# design.net
KiCad netlist of a schematic drawn in Altium Designer
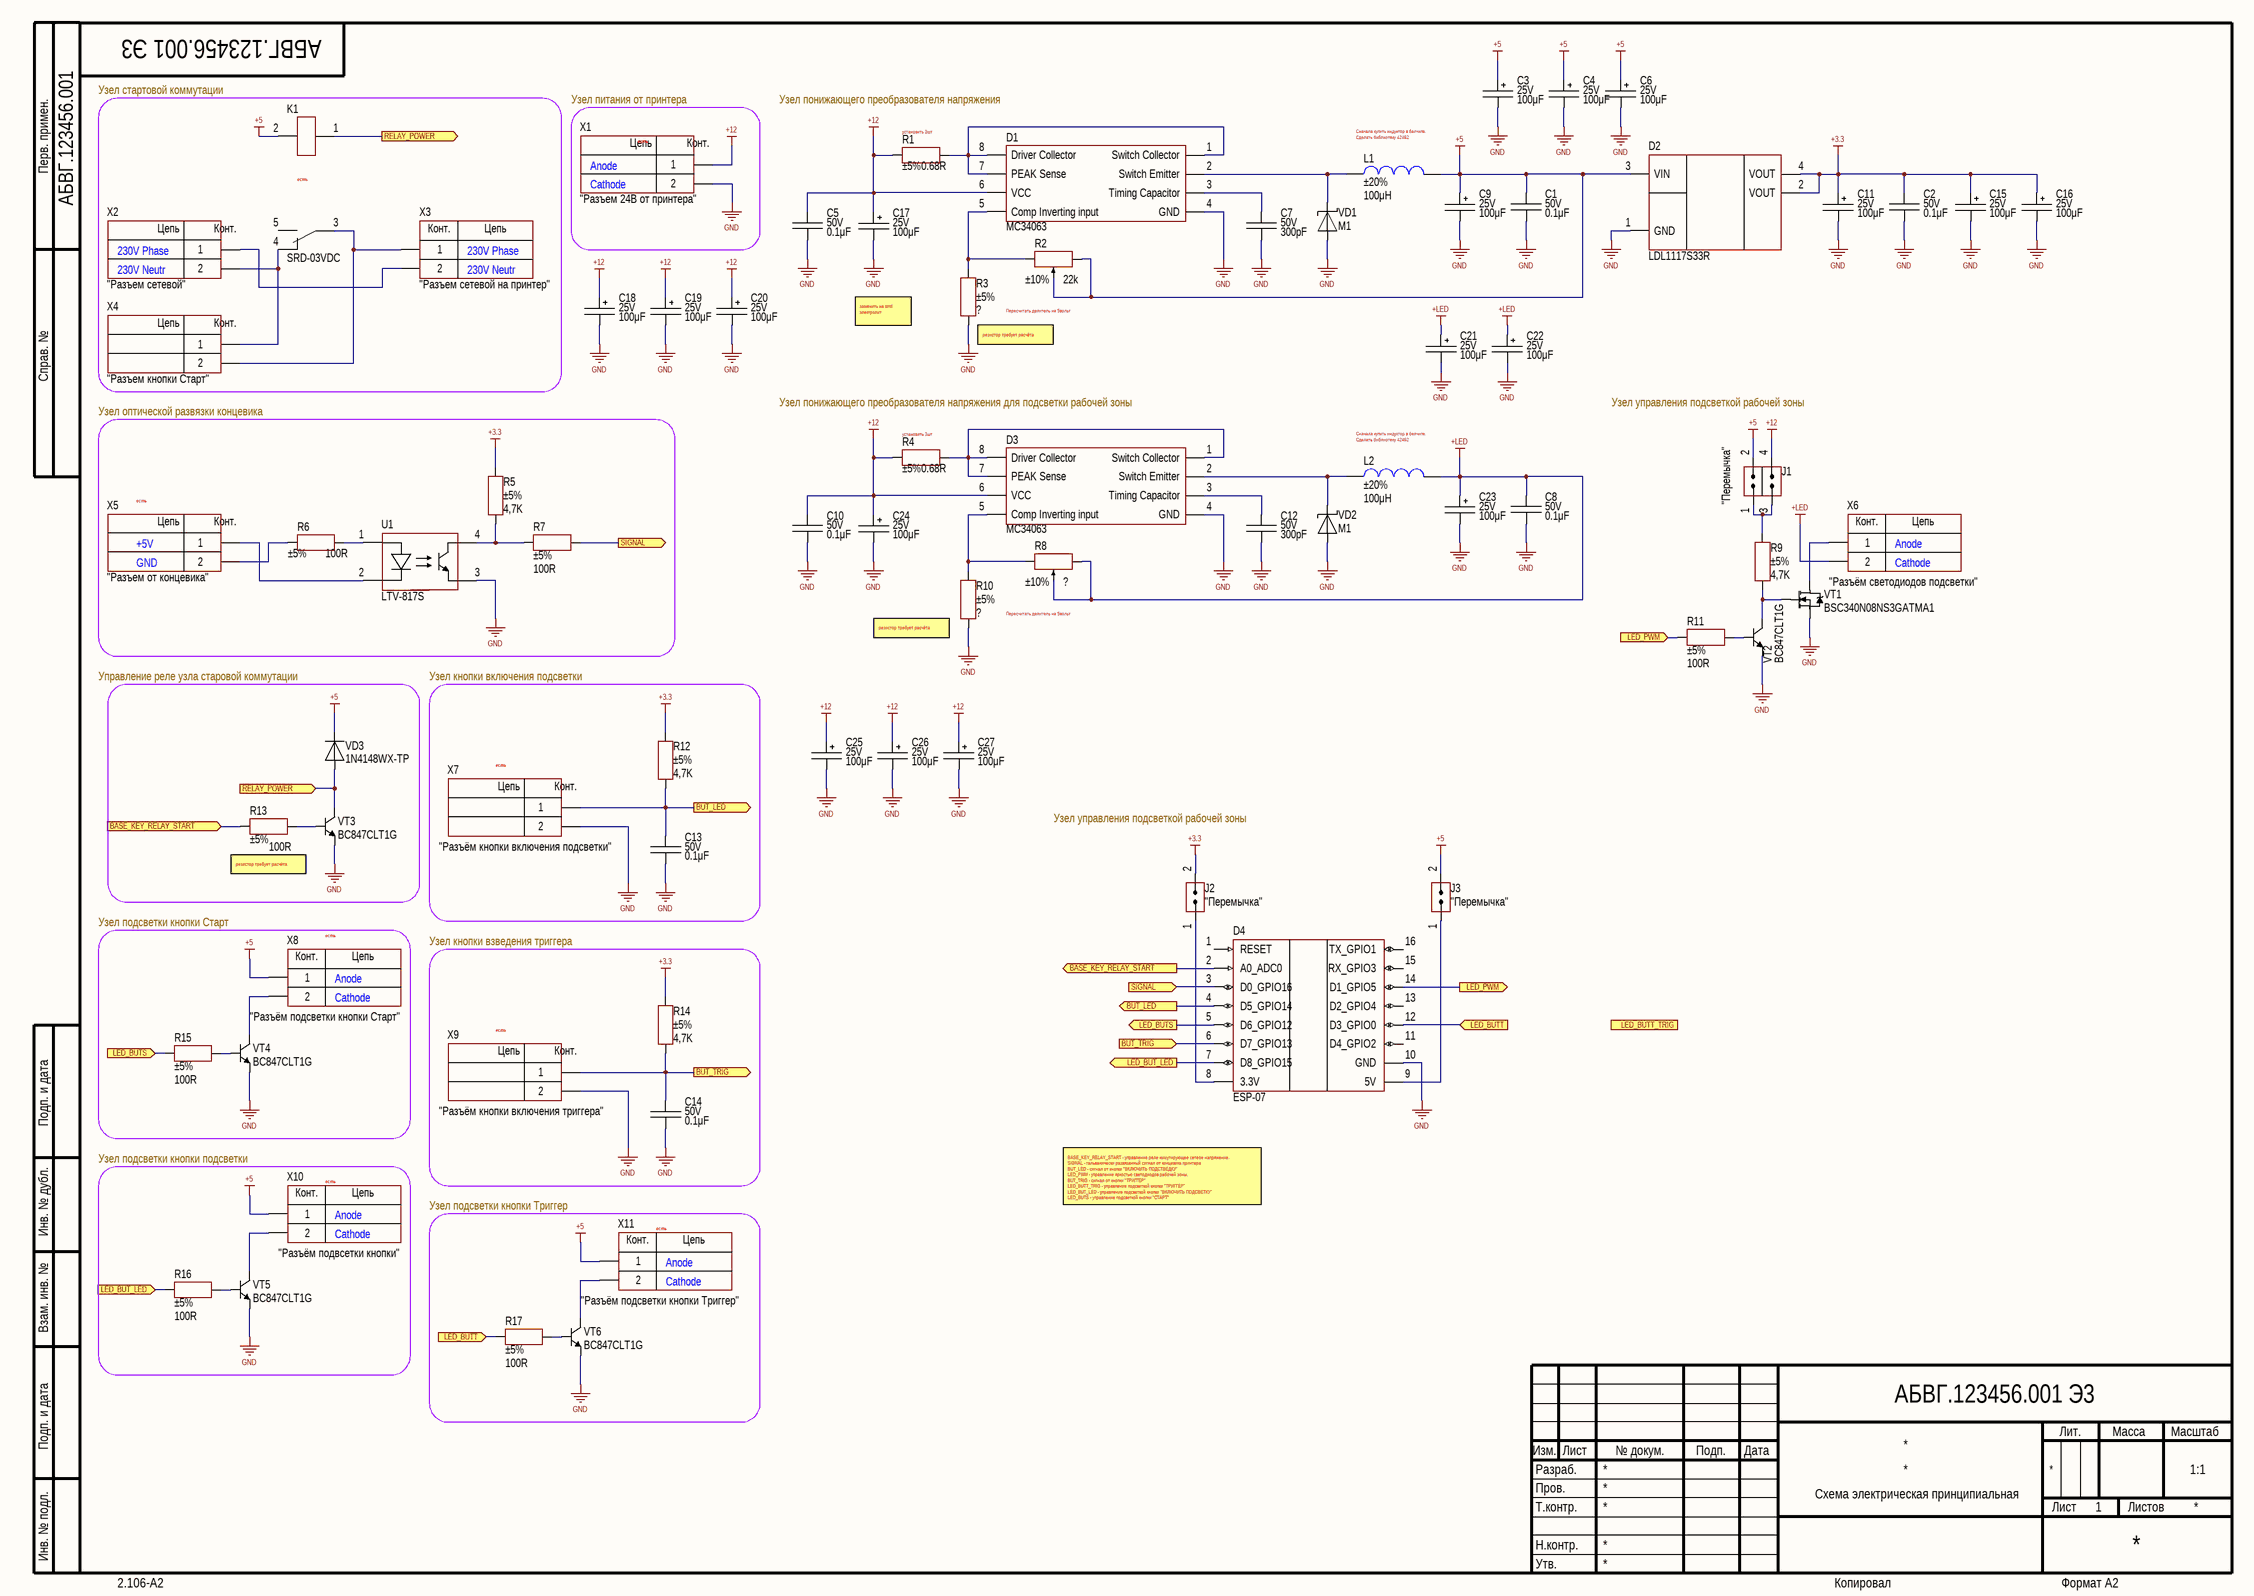
[diagram p0: Схема приинципиальная.SchDoc]

(export (version "E")
  (design (tool "Eeschema 10.0.6"))
  (components
    (comp (ref "C1")
      (value "0.1μF")
      (footprint "CAP: 0603")
      (fields
        (field (name "MANUFACTURER") "Yageo")
        (field (name "PARTNUMBER") "CC0603KRX7R7BB104")
        (field (name "VALUEMANUFACTURERPARTNUMBER") "Ceramic capacitor, 0.1μF, X7R, ±10%, 50V, 0603, -55...+125°C")
        (field (name "VOLTAGE") "50V")
      )
      (libsource (lib "capacitor") (part "Ceramic_0603"))
    )
    (comp (ref "C2")
      (value "0.1μF")
      (footprint "CAP: 0603")
      (fields
        (field (name "MANUFACTURER") "Yageo")
        (field (name "PARTNUMBER") "CC0603KRX7R7BB104")
        (field (name "VALUEMANUFACTURERPARTNUMBER") "Ceramic capacitor, 0.1μF, X7R, ±10%, 50V, 0603, -55...+125°C")
        (field (name "VOLTAGE") "50V")
      )
      (libsource (lib "capacitor") (part "Ceramic_0603"))
    )
    (comp (ref "C3")
      (value "100μF")
      (footprint "CAP: D6.3C2.5H11")
      (fields
        (field (name "MANUFACTURER") "Wurth")
        (field (name "PARTNUMBER") "860080475013")
        (field (name "VALUEMANUFACTURERPARTNUMBER") "Aluminium capacitor, 100μF, 25V, ±20%, 54mOhm, 14x10x5 mm, -55...+105°C")
        (field (name "VOLTAGE") "25V")
      )
      (libsource (lib "capacitor") (part "Aluminium"))
    )
    (comp (ref "C4")
      (value "100μF")
      (footprint "CAP: D6.3C2.5H11")
      (fields
        (field (name "MANUFACTURER") "Wurth")
        (field (name "PARTNUMBER") "860080475013")
        (field (name "VALUEMANUFACTURERPARTNUMBER") "Aluminium capacitor, 100μF, 25V, ±20%, 54mOhm, 14x10x5 mm, -55...+105°C")
        (field (name "VOLTAGE") "25V")
      )
      (libsource (lib "capacitor") (part "Aluminium"))
    )
    (comp (ref "C5")
      (value "0.1μF")
      (footprint "CAP: 0603")
      (fields
        (field (name "MANUFACTURER") "Yageo")
        (field (name "PARTNUMBER") "CC0603KRX7R7BB104")
        (field (name "VALUEMANUFACTURERPARTNUMBER") "Ceramic capacitor, 0.1μF, X7R, ±10%, 50V, 0603, -55...+125°C")
        (field (name "VOLTAGE") "50V")
      )
      (libsource (lib "capacitor") (part "Ceramic_0603"))
    )
    (comp (ref "C6")
      (value "100μF")
      (footprint "CAP: D6.3C2.5H11")
      (fields
        (field (name "MANUFACTURER") "Wurth")
        (field (name "PARTNUMBER") "860080475013")
        (field (name "VALUEMANUFACTURERPARTNUMBER") "Aluminium capacitor, 100μF, 25V, ±20%, 54mOhm, 14x10x5 mm, -55...+105°C")
        (field (name "VOLTAGE") "25V")
      )
      (libsource (lib "capacitor") (part "Aluminium"))
    )
    (comp (ref "C7")
      (value "300pF")
      (footprint "CAP: 0603")
      (fields
        (field (name "MANUFACTURER") "Samsung")
        (field (name "PARTNUMBER") "01584")
        (field (name "VALUEMANUFACTURERPARTNUMBER") "Ceramic capacitor, 300pF, X7R, ±10%, 50V, 0603, -55...+125°C")
        (field (name "VOLTAGE") "50V")
      )
      (libsource (lib "capacitor") (part "Ceramic_0603"))
    )
    (comp (ref "C8")
      (value "0.1μF")
      (footprint "CAP: 0603")
      (fields
        (field (name "MANUFACTURER") "Yageo")
        (field (name "PARTNUMBER") "CC0603KRX7R7BB104")
        (field (name "VALUEMANUFACTURERPARTNUMBER") "Ceramic capacitor, 0.1μF, X7R, ±10%, 50V, 0603, -55...+125°C")
        (field (name "VOLTAGE") "50V")
      )
      (libsource (lib "capacitor") (part "Ceramic_0603"))
    )
    (comp (ref "C9")
      (value "100μF")
      (footprint "CAP: D6.3C2.5H11")
      (fields
        (field (name "MANUFACTURER") "Wurth")
        (field (name "PARTNUMBER") "860080475013")
        (field (name "VALUEMANUFACTURERPARTNUMBER") "Aluminium capacitor, 100μF, 25V, ±20%, 54mOhm, 14x10x5 mm, -55...+105°C")
        (field (name "VOLTAGE") "25V")
      )
      (libsource (lib "capacitor") (part "Aluminium"))
    )
    (comp (ref "C10")
      (value "0.1μF")
      (footprint "CAP: 0603")
      (fields
        (field (name "MANUFACTURER") "Yageo")
        (field (name "PARTNUMBER") "CC0603KRX7R7BB104")
        (field (name "VALUEMANUFACTURERPARTNUMBER") "Ceramic capacitor, 0.1μF, X7R, ±10%, 50V, 0603, -55...+125°C")
        (field (name "VOLTAGE") "50V")
      )
      (libsource (lib "capacitor") (part "Ceramic_0603"))
    )
    (comp (ref "C11")
      (value "100μF")
      (footprint "CAP: D6.3C2.5H11")
      (fields
        (field (name "MANUFACTURER") "Wurth")
        (field (name "PARTNUMBER") "860080475013")
        (field (name "VALUEMANUFACTURERPARTNUMBER") "Aluminium capacitor, 100μF, 25V, ±20%, 54mOhm, 14x10x5 mm, -55...+105°C")
        (field (name "VOLTAGE") "25V")
      )
      (libsource (lib "capacitor") (part "Aluminium"))
    )
    (comp (ref "C12")
      (value "300pF")
      (footprint "CAP: 0603")
      (fields
        (field (name "MANUFACTURER") "Samsung")
        (field (name "PARTNUMBER") "01584")
        (field (name "VALUEMANUFACTURERPARTNUMBER") "Ceramic capacitor, 300pF, X7R, ±10%, 50V, 0603, -55...+125°C")
        (field (name "VOLTAGE") "50V")
      )
      (libsource (lib "capacitor") (part "Ceramic_0603"))
    )
    (comp (ref "C13")
      (value "0.1μF")
      (footprint "CAP: 0603")
      (fields
        (field (name "MANUFACTURER") "Yageo")
        (field (name "PARTNUMBER") "CC0603KRX7R7BB104")
        (field (name "VALUEMANUFACTURERPARTNUMBER") "Ceramic capacitor, 0.1μF, X7R, ±10%, 50V, 0603, -55...+125°C")
        (field (name "VOLTAGE") "50V")
      )
      (libsource (lib "capacitor") (part "Ceramic_0603"))
    )
    (comp (ref "C14")
      (value "0.1μF")
      (footprint "CAP: 0603")
      (fields
        (field (name "MANUFACTURER") "Yageo")
        (field (name "PARTNUMBER") "CC0603KRX7R7BB104")
        (field (name "VALUEMANUFACTURERPARTNUMBER") "Ceramic capacitor, 0.1μF, X7R, ±10%, 50V, 0603, -55...+125°C")
        (field (name "VOLTAGE") "50V")
      )
      (libsource (lib "capacitor") (part "Ceramic_0603"))
    )
    (comp (ref "C15")
      (value "100μF")
      (footprint "CAP: D6.3C2.5H11")
      (fields
        (field (name "MANUFACTURER") "Wurth")
        (field (name "PARTNUMBER") "860080475013")
        (field (name "VALUEMANUFACTURERPARTNUMBER") "Aluminium capacitor, 100μF, 25V, ±20%, 54mOhm, 14x10x5 mm, -55...+105°C")
        (field (name "VOLTAGE") "25V")
      )
      (libsource (lib "capacitor") (part "Aluminium"))
    )
    (comp (ref "C16")
      (value "100μF")
      (footprint "CAP: D6.3C2.5H11")
      (fields
        (field (name "MANUFACTURER") "Wurth")
        (field (name "PARTNUMBER") "860080475013")
        (field (name "VALUEMANUFACTURERPARTNUMBER") "Aluminium capacitor, 100μF, 25V, ±20%, 54mOhm, 14x10x5 mm, -55...+105°C")
        (field (name "VOLTAGE") "25V")
      )
      (libsource (lib "capacitor") (part "Aluminium"))
    )
    (comp (ref "C17")
      (value "100μF")
      (footprint "CAP: D6.3C2.5H11")
      (fields
        (field (name "MANUFACTURER") "Wurth")
        (field (name "PARTNUMBER") "860080475013")
        (field (name "VALUEMANUFACTURERPARTNUMBER") "Aluminium capacitor, 100μF, 25V, ±20%, 54mOhm, 14x10x5 mm, -55...+105°C")
        (field (name "VOLTAGE") "25V")
      )
      (libsource (lib "capacitor") (part "Aluminium"))
    )
    (comp (ref "C18")
      (value "100μF")
      (footprint "CAP: D6.3C2.5H11")
      (fields
        (field (name "MANUFACTURER") "Wurth")
        (field (name "PARTNUMBER") "860080475013")
        (field (name "VALUEMANUFACTURERPARTNUMBER") "Aluminium capacitor, 100μF, 25V, ±20%, 54mOhm, 14x10x5 mm, -55...+105°C")
        (field (name "VOLTAGE") "25V")
      )
      (libsource (lib "capacitor") (part "Aluminium"))
    )
    (comp (ref "C19")
      (value "100μF")
      (footprint "CAP: D6.3C2.5H11")
      (fields
        (field (name "MANUFACTURER") "Wurth")
        (field (name "PARTNUMBER") "860080475013")
        (field (name "VALUEMANUFACTURERPARTNUMBER") "Aluminium capacitor, 100μF, 25V, ±20%, 54mOhm, 14x10x5 mm, -55...+105°C")
        (field (name "VOLTAGE") "25V")
      )
      (libsource (lib "capacitor") (part "Aluminium"))
    )
    (comp (ref "C20")
      (value "100μF")
      (footprint "CAP: D6.3C2.5H11")
      (fields
        (field (name "MANUFACTURER") "Wurth")
        (field (name "PARTNUMBER") "860080475013")
        (field (name "VALUEMANUFACTURERPARTNUMBER") "Aluminium capacitor, 100μF, 25V, ±20%, 54mOhm, 14x10x5 mm, -55...+105°C")
        (field (name "VOLTAGE") "25V")
      )
      (libsource (lib "capacitor") (part "Aluminium"))
    )
    (comp (ref "C21")
      (value "100μF")
      (footprint "CAP: D6.3C2.5H11")
      (fields
        (field (name "MANUFACTURER") "Wurth")
        (field (name "PARTNUMBER") "860080475013")
        (field (name "VALUEMANUFACTURERPARTNUMBER") "Aluminium capacitor, 100μF, 25V, ±20%, 54mOhm, 14x10x5 mm, -55...+105°C")
        (field (name "VOLTAGE") "25V")
      )
      (libsource (lib "capacitor") (part "Aluminium"))
    )
    (comp (ref "C22")
      (value "100μF")
      (footprint "CAP: D6.3C2.5H11")
      (fields
        (field (name "MANUFACTURER") "Wurth")
        (field (name "PARTNUMBER") "860080475013")
        (field (name "VALUEMANUFACTURERPARTNUMBER") "Aluminium capacitor, 100μF, 25V, ±20%, 54mOhm, 14x10x5 mm, -55...+105°C")
        (field (name "VOLTAGE") "25V")
      )
      (libsource (lib "capacitor") (part "Aluminium"))
    )
    (comp (ref "C23")
      (value "100μF")
      (footprint "CAP: D6.3C2.5H11")
      (fields
        (field (name "MANUFACTURER") "Wurth")
        (field (name "PARTNUMBER") "860080475013")
        (field (name "VALUEMANUFACTURERPARTNUMBER") "Aluminium capacitor, 100μF, 25V, ±20%, 54mOhm, 14x10x5 mm, -55...+105°C")
        (field (name "VOLTAGE") "25V")
      )
      (libsource (lib "capacitor") (part "Aluminium"))
    )
    (comp (ref "C24")
      (value "100μF")
      (footprint "CAP: D6.3C2.5H11")
      (fields
        (field (name "MANUFACTURER") "Wurth")
        (field (name "PARTNUMBER") "860080475013")
        (field (name "VALUEMANUFACTURERPARTNUMBER") "Aluminium capacitor, 100μF, 25V, ±20%, 54mOhm, 14x10x5 mm, -55...+105°C")
        (field (name "VOLTAGE") "25V")
      )
      (libsource (lib "capacitor") (part "Aluminium"))
    )
    (comp (ref "C25")
      (value "100μF")
      (footprint "CAP: D6.3C2.5H11")
      (fields
        (field (name "MANUFACTURER") "Wurth")
        (field (name "PARTNUMBER") "860080475013")
        (field (name "VALUEMANUFACTURERPARTNUMBER") "Aluminium capacitor, 100μF, 25V, ±20%, 54mOhm, 14x10x5 mm, -55...+105°C")
        (field (name "VOLTAGE") "25V")
      )
      (libsource (lib "capacitor") (part "Aluminium"))
    )
    (comp (ref "C26")
      (value "100μF")
      (footprint "CAP: D6.3C2.5H11")
      (fields
        (field (name "MANUFACTURER") "Wurth")
        (field (name "PARTNUMBER") "860080475013")
        (field (name "VALUEMANUFACTURERPARTNUMBER") "Aluminium capacitor, 100μF, 25V, ±20%, 54mOhm, 14x10x5 mm, -55...+105°C")
        (field (name "VOLTAGE") "25V")
      )
      (libsource (lib "capacitor") (part "Aluminium"))
    )
    (comp (ref "C27")
      (value "100μF")
      (footprint "CAP: D6.3C2.5H11")
      (fields
        (field (name "MANUFACTURER") "Wurth")
        (field (name "PARTNUMBER") "860080475013")
        (field (name "VALUEMANUFACTURERPARTNUMBER") "Aluminium capacitor, 100μF, 25V, ±20%, 54mOhm, 14x10x5 mm, -55...+105°C")
        (field (name "VOLTAGE") "25V")
      )
      (libsource (lib "capacitor") (part "Aluminium"))
    )
    (comp (ref "D1")
      (value "~")
      (footprint "8-SOIC")
      (description "DC TO DC CONVERTER\r\nCONTROLLER")
      (fields
        (field (name "MANUFACTURER") "UTC")
        (field (name "VALUEMANUFACTURERPARTNUMBER") "DC TO DC CONVERTER, max supply 40V, Open drain, -40...+105°C, 8-SOIC")
        (field (name "PARTNUMBER") "MC34063")
      )
      (libsource (lib "ic-power-supply") (part "MC34063"))
    )
    (comp (ref "D2")
      (value "~")
      (footprint "SOT223")
      (description "Linear voltage regulator")
      (fields
        (field (name "MANUFACTURER") "STMicroelectronics")
        (field (name "VALUEMANUFACTURERPARTNUMBER") "Linear voltage regulator, input 3.9...18V, 0.6V, output 3.3V, 1.2A, -40...+85°C, SOT223")
        (field (name "PARTNUMBER") "LDL1117S33R")
      )
      (libsource (lib "ic-power-supply") (part "LDL1117S33R"))
    )
    (comp (ref "D3")
      (value "~")
      (footprint "8-SOIC")
      (description "DC TO DC CONVERTER\r\nCONTROLLER")
      (fields
        (field (name "MANUFACTURER") "UTC")
        (field (name "VALUEMANUFACTURERPARTNUMBER") "DC TO DC CONVERTER, max supply 40V, Open drain, -40...+105°C, 8-SOIC")
        (field (name "PARTNUMBER") "MC34063")
      )
      (libsource (lib "ic-power-supply") (part "MC34063"))
    )
    (comp (ref "D4")
      (value "~")
      (footprint "ESP8266MOD D1 mini")
      (description "module")
      (fields
        (field (name "MANUFACTURER") "Espressif Systems")
        (field (name "VALUEMANUFACTURERPARTNUMBER") "Wi-Fi module, 802.11 b/g/n, 8 bit, SDIO/SPI/UART, -40...+85°C, 21x16mm")
        (field (name "PARTNUMBER") "ESP-07")
      )
      (libsource (lib "module") (part "ESP8266MOD D1 mini"))
    )
    (comp (ref "J1")
      (value "~")
      (footprint "CON: JUMPER x2")
      (fields (field (name "COMMENTTEXT") "\"Перемычка\""))
      (libsource (lib "connector") (part "Jumper_double"))
    )
    (comp (ref "J2")
      (value "~")
      (footprint "CON: JUMPER x1")
      (fields (field (name "COMMENTTEXT") "\"Перемычка\""))
      (libsource (lib "connector") (part "Jumper_single"))
    )
    (comp (ref "J3")
      (value "~")
      (footprint "CON: JUMPER x1")
      (fields (field (name "COMMENTTEXT") "\"Перемычка\""))
      (libsource (lib "connector") (part "Jumper_single"))
    )
    (comp (ref "K1")
      (value "~")
      (footprint "REL: SRD-03VDC")
      (fields
        (field (name "MANUFACTURER") "Ningbo Songle")
        (field (name "VALUEMANUFACTURERPARTNUMBER") "Electromechanics relay, 3VDC, 250VAC, 10A, 1NO, -40...+85°C")
        (field (name "PARTNUMBER") "SRD-03VDC")
      )
      (libsource (lib "electromechanics") (part "Relay_SRD-03VDC"))
    )
    (comp (ref "L1")
      (value "100μH")
      (footprint "CDRH")
      (fields
        (field (name "MANUFACTURER") "Bourns")
        (field (name "PARTNUMBER") "CDRH")
        (field (name "VALUEMANUFACTURERPARTNUMBER") "Fixed inductor, 100μH, ±20%, CDRH101R, 3A, -40...+150°C")
        (field (name "TOLERANCE") "±20%")
      )
      (libsource (lib "inductor") (part "Inductor_CDRH"))
    )
    (comp (ref "L2")
      (value "100μH")
      (footprint "CDRH")
      (fields
        (field (name "MANUFACTURER") "Bourns")
        (field (name "PARTNUMBER") "CDRH")
        (field (name "VALUEMANUFACTURERPARTNUMBER") "Fixed inductor, 100μH, ±20%, CDRH101R, 3A, -40...+150°C")
        (field (name "TOLERANCE") "±20%")
      )
      (libsource (lib "inductor") (part "Inductor_CDRH"))
    )
    (comp (ref "R1")
      (value "0.68R")
      (footprint "RES: 2512")
      (fields
        (field (name "MANUFACTURER") "Yageo")
        (field (name "PARTNUMBER") "RC2512JK-07100RL")
        (field (name "VALUEMANUFACTURERPARTNUMBER") "Resistor film, 0.68R, ±5%, 2512, 1W, -55...+125°C")
        (field (name "TOLERANCE") "±5%")
      )
      (libsource (lib "resistor") (part "Resistor_2512"))
    )
    (comp (ref "R2")
      (value "22k")
      (footprint "RES: 3296W")
      (fields
        (field (name "MANUFACTURER") "Bourns")
        (field (name "PARTNUMBER") "3296W-1-103LF")
        (field (name "VALUEMANUFACTURERPARTNUMBER") "Resistor film, 22k, ±10%, 3296W, 0.5W, -55...+125°C")
        (field (name "TOLERANCE") "±10%")
      )
      (libsource (lib "resistor") (part "Trimmer"))
    )
    (comp (ref "R3")
      (value "?")
      (footprint "RES: 0603")
      (fields
        (field (name "MANUFACTURER") "Yageo")
        (field (name "PARTNUMBER") "RC0603JR-07100RL")
        (field (name "VALUEMANUFACTURERPARTNUMBER") "Resistor film, ?, ±5%, 0603, 0.1W, -55...+125°C")
        (field (name "TOLERANCE") "±5%")
      )
      (libsource (lib "") (part "Resistor_0603_1"))
    )
    (comp (ref "R4")
      (value "0.68R")
      (footprint "RES: 2512")
      (fields
        (field (name "MANUFACTURER") "Yageo")
        (field (name "PARTNUMBER") "RC2512JK-07100RL")
        (field (name "VALUEMANUFACTURERPARTNUMBER") "Resistor film, 0.68R, ±5%, 2512, 1W, -55...+125°C")
        (field (name "TOLERANCE") "±5%")
      )
      (libsource (lib "resistor") (part "Resistor_2512"))
    )
    (comp (ref "R5")
      (value "4,7K")
      (footprint "RES: 0603")
      (fields
        (field (name "MANUFACTURER") "Yageo")
        (field (name "PARTNUMBER") "RC0603JR-07100RL")
        (field (name "VALUEMANUFACTURERPARTNUMBER") "Resistor film, 4,7K, ±5%, 0603, 0.1W, -55...+125°C")
        (field (name "TOLERANCE") "±5%")
      )
      (libsource (lib "") (part "Resistor_0603_1"))
    )
    (comp (ref "R6")
      (value "100R")
      (footprint "RES: 0603")
      (fields
        (field (name "MANUFACTURER") "Yageo")
        (field (name "PARTNUMBER") "RC0603JR-07100RL")
        (field (name "VALUEMANUFACTURERPARTNUMBER") "Resistor film, 100R, ±5%, 0603, 0.1W, -55...+125°C")
        (field (name "TOLERANCE") "±5%")
      )
      (libsource (lib "") (part "Resistor_0603_2"))
    )
    (comp (ref "R7")
      (value "100R")
      (footprint "RES: 0603")
      (fields
        (field (name "MANUFACTURER") "Yageo")
        (field (name "PARTNUMBER") "RC0603JR-07100RL")
        (field (name "VALUEMANUFACTURERPARTNUMBER") "Resistor film, 100R, ±5%, 0603, 0.1W, -55...+125°C")
        (field (name "TOLERANCE") "±5%")
      )
      (libsource (lib "resistor") (part "Resistor_0603"))
    )
    (comp (ref "R8")
      (value "?")
      (footprint "RES: 3296W")
      (fields
        (field (name "MANUFACTURER") "Bourns")
        (field (name "PARTNUMBER") "3296W-1-103LF")
        (field (name "VALUEMANUFACTURERPARTNUMBER") "Resistor film, ?, ±10%, 3296W, 0.5W, -55...+125°C")
        (field (name "TOLERANCE") "±10%")
      )
      (libsource (lib "resistor") (part "Trimmer"))
    )
    (comp (ref "R9")
      (value "4,7K")
      (footprint "RES: 0603")
      (fields
        (field (name "MANUFACTURER") "Yageo")
        (field (name "PARTNUMBER") "RC0603JR-07100RL")
        (field (name "VALUEMANUFACTURERPARTNUMBER") "Resistor film, 4,7K, ±5%, 0603, 0.1W, -55...+125°C")
        (field (name "TOLERANCE") "±5%")
      )
      (libsource (lib "") (part "Resistor_0603_1"))
    )
    (comp (ref "R10")
      (value "?")
      (footprint "RES: 0603")
      (fields
        (field (name "MANUFACTURER") "Yageo")
        (field (name "PARTNUMBER") "RC0603JR-07100RL")
        (field (name "VALUEMANUFACTURERPARTNUMBER") "Resistor film, ?, ±5%, 0603, 0.1W, -55...+125°C")
        (field (name "TOLERANCE") "±5%")
      )
      (libsource (lib "") (part "Resistor_0603_1"))
    )
    (comp (ref "R11")
      (value "100R")
      (footprint "RES: 0603")
      (fields
        (field (name "MANUFACTURER") "Yageo")
        (field (name "PARTNUMBER") "RC0603JR-07100RL")
        (field (name "VALUEMANUFACTURERPARTNUMBER") "Resistor film, 100R, ±5%, 0603, 0.1W, -55...+125°C")
        (field (name "TOLERANCE") "±5%")
      )
      (libsource (lib "resistor") (part "Resistor_0603"))
    )
    (comp (ref "R12")
      (value "4,7K")
      (footprint "RES: 0603")
      (fields
        (field (name "MANUFACTURER") "Yageo")
        (field (name "PARTNUMBER") "RC0603JR-07100RL")
        (field (name "VALUEMANUFACTURERPARTNUMBER") "Resistor film, 4,7K, ±5%, 0603, 0.1W, -55...+125°C")
        (field (name "TOLERANCE") "±5%")
      )
      (libsource (lib "") (part "Resistor_0603_1"))
    )
    (comp (ref "R13")
      (value "100R")
      (footprint "RES: 0603")
      (fields
        (field (name "MANUFACTURER") "Yageo")
        (field (name "PARTNUMBER") "RC0603JR-07100RL")
        (field (name "VALUEMANUFACTURERPARTNUMBER") "Resistor film, 100R, ±5%, 0603, 0.1W, -55...+125°C")
        (field (name "TOLERANCE") "±5%")
      )
      (libsource (lib "resistor") (part "Resistor_0603"))
    )
    (comp (ref "R14")
      (value "4,7K")
      (footprint "RES: 0603")
      (fields
        (field (name "MANUFACTURER") "Yageo")
        (field (name "PARTNUMBER") "RC0603JR-07100RL")
        (field (name "VALUEMANUFACTURERPARTNUMBER") "Resistor film, 4,7K, ±5%, 0603, 0.1W, -55...+125°C")
        (field (name "TOLERANCE") "±5%")
      )
      (libsource (lib "") (part "Resistor_0603_1"))
    )
    (comp (ref "R15")
      (value "100R")
      (footprint "RES: 0603")
      (fields
        (field (name "MANUFACTURER") "Yageo")
        (field (name "PARTNUMBER") "RC0603JR-07100RL")
        (field (name "VALUEMANUFACTURERPARTNUMBER") "Resistor film, 100R, ±5%, 0603, 0.1W, -55...+125°C")
        (field (name "TOLERANCE") "±5%")
      )
      (libsource (lib "resistor") (part "Resistor_0603"))
    )
    (comp (ref "R16")
      (value "100R")
      (footprint "RES: 0603")
      (fields
        (field (name "MANUFACTURER") "Yageo")
        (field (name "PARTNUMBER") "RC0603JR-07100RL")
        (field (name "VALUEMANUFACTURERPARTNUMBER") "Resistor film, 100R, ±5%, 0603, 0.1W, -55...+125°C")
        (field (name "TOLERANCE") "±5%")
      )
      (libsource (lib "resistor") (part "Resistor_0603"))
    )
    (comp (ref "R17")
      (value "100R")
      (footprint "RES: 0603")
      (fields
        (field (name "MANUFACTURER") "Yageo")
        (field (name "PARTNUMBER") "RC0603JR-07100RL")
        (field (name "VALUEMANUFACTURERPARTNUMBER") "Resistor film, 100R, ±5%, 0603, 0.1W, -55...+125°C")
        (field (name "TOLERANCE") "±5%")
      )
      (libsource (lib "resistor") (part "Resistor_0603"))
    )
    (comp (ref "U1")
      (value "~")
      (footprint "4-DIP")
      (description "Optoisolator")
      (fields
        (field (name "MANUFACTURER") "Lite-On")
        (field (name "VALUEMANUFACTURERPARTNUMBER") "IC optoisolator, 4µs/3µs, 5000Vrms, 35V, -40...+125°C, 4-SMD")
        (field (name "PARTNUMBER") "LTV-817S")
      )
      (libsource (lib "optoisolator") (part "LTV-817"))
    )
    (comp (ref "VD1")
      (value "~")
      (footprint "DIODE: SMA")
      (fields
        (field (name "MANUFACTURER") "Diodes Incorporated")
        (field (name "VALUEMANUFACTURERPARTNUMBER") "Schottky diode, 50V, 1000mA, 1V, 15pF, SOD-123, -55...+150°C")
        (field (name "VOLTAGE") "50V")
        (field (name "PARTNUMBER") "M1")
      )
      (libsource (lib "diode") (part "Schottky_single"))
    )
    (comp (ref "VD2")
      (value "~")
      (footprint "DIODE: SMA")
      (fields
        (field (name "MANUFACTURER") "Diodes Incorporated")
        (field (name "VALUEMANUFACTURERPARTNUMBER") "Schottky diode, 50V, 1000mA, 1V, 15pF, SOD-123, -55...+150°C")
        (field (name "VOLTAGE") "50V")
        (field (name "PARTNUMBER") "M1")
      )
      (libsource (lib "diode") (part "Schottky_single"))
    )
    (comp (ref "VD3")
      (value "~")
      (footprint "DIODE: SMA")
      (fields
        (field (name "MANUFACTURER") "Micro Commercial")
        (field (name "VALUEMANUFACTURERPARTNUMBER") "Single diode, 75V, 150mA, 1V, 4ns, SOD-323, -55...+150°C")
        (field (name "VOLTAGE") "75V")
        (field (name "PARTNUMBER") "1N4148WX-TP")
      )
      (libsource (lib "diode") (part "Diode_single"))
    )
    (comp (ref "VT1")
      (value "~")
      (footprint "DPAK")
      (fields
        (field (name "MANUFACTURER") "Infineon Technologies")
        (field (name "VALUEMANUFACTURERPARTNUMBER") "MOSFET N-channel transistor, 80V, 7A, 9.1nC, 2.5W, 34mOhm, 756pF, 8-TDSON, -55...+150°C")
        (field (name "PARTNUMBER") "BSC340N08NS3GATMA1")
      )
      (libsource (lib "transistor") (part "MOSFET_N_123"))
    )
    (comp (ref "VT2")
      (value "~")
      (footprint "SOT23")
      (fields
        (field (name "MANUFACTURER") "ON Semiconductor")
        (field (name "VALUEMANUFACTURERPARTNUMBER") "NPN transistor, 45V, 100mA, 100MHz, 300mW, 0.6V, 420, SOT-23, -55...+125°C")
        (field (name "PARTNUMBER") "BC847CLT1G")
      )
      (libsource (lib "transistor") (part "BJT_NPN_132"))
    )
    (comp (ref "VT3")
      (value "~")
      (footprint "SOT23")
      (fields
        (field (name "MANUFACTURER") "ON Semiconductor")
        (field (name "VALUEMANUFACTURERPARTNUMBER") "NPN transistor, 45V, 100mA, 100MHz, 300mW, 0.6V, 420, SOT-23, -55...+125°C")
        (field (name "PARTNUMBER") "BC847CLT1G")
      )
      (libsource (lib "transistor") (part "BJT_NPN_132"))
    )
    (comp (ref "VT4")
      (value "~")
      (footprint "SOT23")
      (fields
        (field (name "MANUFACTURER") "ON Semiconductor")
        (field (name "VALUEMANUFACTURERPARTNUMBER") "NPN transistor, 45V, 100mA, 100MHz, 300mW, 0.6V, 420, SOT-23, -55...+125°C")
        (field (name "PARTNUMBER") "BC847CLT1G")
      )
      (libsource (lib "transistor") (part "BJT_NPN_132"))
    )
    (comp (ref "VT5")
      (value "~")
      (footprint "SOT23")
      (fields
        (field (name "MANUFACTURER") "ON Semiconductor")
        (field (name "VALUEMANUFACTURERPARTNUMBER") "NPN transistor, 45V, 100mA, 100MHz, 300mW, 0.6V, 420, SOT-23, -55...+125°C")
        (field (name "PARTNUMBER") "BC847CLT1G")
      )
      (libsource (lib "transistor") (part "BJT_NPN_132"))
    )
    (comp (ref "VT6")
      (value "~")
      (footprint "SOT23")
      (fields
        (field (name "MANUFACTURER") "ON Semiconductor")
        (field (name "VALUEMANUFACTURERPARTNUMBER") "NPN transistor, 45V, 100mA, 100MHz, 300mW, 0.6V, 420, SOT-23, -55...+125°C")
        (field (name "PARTNUMBER") "BC847CLT1G")
      )
      (libsource (lib "transistor") (part "BJT_NPN_132"))
    )
    (comp (ref "X1")
      (value "~")
      (footprint "CON: DG301-5.0-02P-12-00AH")
      (fields
        (field (name "MANUFACTURER") "Degson")
        (field (name "VALUEMANUFACTURERPARTNUMBER") "Terminal connector, 2pin, 3.5mm, 300VAC, 10A")
        (field (name "PARTNUMBER") "DG350-3.5-02P-14")
        (field (name "COMMENTTEXT") "\"Разъем 24В от принтера\"")
      )
      (libsource (lib "") (part "Connector_terminal_2pin_1"))
    )
    (comp (ref "X2")
      (value "~")
      (footprint "CON: DG301-5.0-02P-12-00AH")
      (fields
        (field (name "MANUFACTURER") "Degson")
        (field (name "VALUEMANUFACTURERPARTNUMBER") "Terminal connector, 2pin, 3.5mm, 300VAC, 10A")
        (field (name "PARTNUMBER") "DG350-3.5-02P-14")
        (field (name "COMMENTTEXT") "\"Разъем сетевой\"")
      )
      (libsource (lib "") (part "Connector_terminal_2pin_1"))
    )
    (comp (ref "X3")
      (value "~")
      (footprint "CON: DG301-5.0-02P-12-00AH")
      (fields
        (field (name "MANUFACTURER") "Degson")
        (field (name "VALUEMANUFACTURERPARTNUMBER") "Terminal connector, 2pin, 3.5mm, 300VAC, 10A")
        (field (name "PARTNUMBER") "DG350-3.5-02P-14")
        (field (name "COMMENTTEXT") "\"Разъем сетевой на принтер\"")
      )
      (libsource (lib "connector") (part "Connector_terminal_2pin"))
    )
    (comp (ref "X4")
      (value "~")
      (footprint "CON: DG301-5.0-02P-12-00AH")
      (fields
        (field (name "MANUFACTURER") "Degson")
        (field (name "VALUEMANUFACTURERPARTNUMBER") "Terminal connector, 2pin, 3.5mm, 300VAC, 10A")
        (field (name "PARTNUMBER") "DG350-3.5-02P-14")
        (field (name "COMMENTTEXT") "\"Разъем кнопки Старт\"")
      )
      (libsource (lib "") (part "Connector_terminal_2pin_1"))
    )
    (comp (ref "X5")
      (value "~")
      (footprint "CON: DG301-5.0-02P-12-00AH")
      (fields
        (field (name "MANUFACTURER") "Degson")
        (field (name "VALUEMANUFACTURERPARTNUMBER") "Terminal connector, 2pin, 3.5mm, 300VAC, 10A")
        (field (name "PARTNUMBER") "DG350-3.5-02P-14")
        (field (name "COMMENTTEXT") "\"Разъем от концевика\"")
      )
      (libsource (lib "") (part "Connector_terminal_2pin_1"))
    )
    (comp (ref "X6")
      (value "~")
      (footprint "CON: DG301-5.0-02P-12-00AH")
      (fields
        (field (name "MANUFACTURER") "Degson")
        (field (name "VALUEMANUFACTURERPARTNUMBER") "Terminal connector, 2pin, 3.5mm, 300VAC, 10A")
        (field (name "PARTNUMBER") "DG350-3.5-02P-14")
        (field (name "COMMENTTEXT") "\"Разъём светодиодов подсветки\"")
      )
      (libsource (lib "connector") (part "Connector_terminal_2pin"))
    )
    (comp (ref "X7")
      (value "~")
      (footprint "CON: DG301-5.0-02P-12-00AH")
      (fields
        (field (name "MANUFACTURER") "Degson")
        (field (name "VALUEMANUFACTURERPARTNUMBER") "Terminal connector, 2pin, 3.5mm, 300VAC, 10A")
        (field (name "PARTNUMBER") "DG350-3.5-02P-14")
        (field (name "COMMENTTEXT") "\"Разъём кнопки включения подсветки\"")
      )
      (libsource (lib "") (part "Connector_terminal_2pin_1"))
    )
    (comp (ref "X8")
      (value "~")
      (footprint "CON: DG301-5.0-02P-12-00AH")
      (fields
        (field (name "MANUFACTURER") "Degson")
        (field (name "VALUEMANUFACTURERPARTNUMBER") "Terminal connector, 2pin, 3.5mm, 300VAC, 10A")
        (field (name "PARTNUMBER") "DG350-3.5-02P-14")
        (field (name "COMMENTTEXT") "\"Разъём подсветки кнопки Старт\"")
      )
      (libsource (lib "connector") (part "Connector_terminal_2pin"))
    )
    (comp (ref "X9")
      (value "~")
      (footprint "CON: DG301-5.0-02P-12-00AH")
      (fields
        (field (name "MANUFACTURER") "Degson")
        (field (name "VALUEMANUFACTURERPARTNUMBER") "Terminal connector, 2pin, 3.5mm, 300VAC, 10A")
        (field (name "PARTNUMBER") "DG350-3.5-02P-14")
        (field (name "COMMENTTEXT") "\"Разъём кнопки включения триггера\"")
      )
      (libsource (lib "") (part "Connector_terminal_2pin_1"))
    )
    (comp (ref "X10")
      (value "~")
      (footprint "CON: DG301-5.0-02P-12-00AH")
      (fields
        (field (name "MANUFACTURER") "Degson")
        (field (name "VALUEMANUFACTURERPARTNUMBER") "Terminal connector, 2pin, 3.5mm, 300VAC, 10A")
        (field (name "PARTNUMBER") "DG350-3.5-02P-14")
        (field (name "COMMENTTEXT") "\"Разъём подвсетки кнопки\"")
      )
      (libsource (lib "connector") (part "Connector_terminal_2pin"))
    )
    (comp (ref "X11")
      (value "~")
      (footprint "CON: DG301-5.0-02P-12-00AH")
      (fields
        (field (name "MANUFACTURER") "Degson")
        (field (name "VALUEMANUFACTURERPARTNUMBER") "Terminal connector, 2pin, 3.5mm, 300VAC, 10A")
        (field (name "PARTNUMBER") "DG350-3.5-02P-14")
        (field (name "COMMENTTEXT") "\"Разъём подсветки кнопки Триггер\"")
      )
      (libsource (lib "connector") (part "Connector_terminal_2pin"))
    )
  )
  (nets
    (net (code "1") (name "+3.3") (class "Default")
      (node (ref "C11") (pin "1") (pinfunction "1_1") (pintype "passive"))
      (node (ref "C15") (pin "1") (pinfunction "1_1") (pintype "passive"))
      (node (ref "C16") (pin "1") (pinfunction "1_1") (pintype "passive"))
      (node (ref "C2") (pin "2") (pinfunction "2_2") (pintype "passive"))
      (node (ref "D2") (pin "2") (pinfunction "VOUT_2") (pintype "power_in"))
      (node (ref "D2") (pin "4") (pinfunction "VOUT_4") (pintype "power_in"))
      (node (ref "J2") (pin "2") (pinfunction "IN_2") (pintype "passive"))
      (node (ref "R12") (pin "2") (pinfunction "2_2") (pintype "passive"))
      (node (ref "R14") (pin "2") (pinfunction "2_2") (pintype "passive"))
      (node (ref "R5") (pin "2") (pinfunction "2_2") (pintype "passive"))
    )
    (net (code "2") (name "+5") (class "Default")
      (node (ref "C1") (pin "2") (pinfunction "2_2") (pintype "passive"))
      (node (ref "C3") (pin "1") (pinfunction "1_1") (pintype "passive"))
      (node (ref "C4") (pin "1") (pinfunction "1_1") (pintype "passive"))
      (node (ref "C6") (pin "1") (pinfunction "1_1") (pintype "passive"))
      (node (ref "C9") (pin "1") (pinfunction "1_1") (pintype "passive"))
      (node (ref "D2") (pin "3") (pinfunction "VIN_3") (pintype "power_in"))
      (node (ref "J1") (pin "2") (pinfunction "IN_2") (pintype "passive"))
      (node (ref "J3") (pin "2") (pinfunction "IN_2") (pintype "passive"))
      (node (ref "K1") (pin "2") (pinfunction "2_2") (pintype "passive"))
      (node (ref "L1") (pin "1") (pinfunction "1_1") (pintype "passive"))
      (node (ref "R2") (pin "1") (pinfunction "1_1") (pintype "passive"))
      (node (ref "R2") (pin "2") (pinfunction "2_2") (pintype "passive"))
      (node (ref "VD3") (pin "2") (pinfunction "2_2") (pintype "passive"))
      (node (ref "X10") (pin "1") (pinfunction "1_1") (pintype "passive"))
      (node (ref "X11") (pin "1") (pinfunction "1_1") (pintype "passive"))
      (node (ref "X8") (pin "1") (pinfunction "1_1") (pintype "passive"))
    )
    (net (code "3") (name "+12") (class "Default")
      (node (ref "C10") (pin "2") (pinfunction "2_2") (pintype "passive"))
      (node (ref "C17") (pin "1") (pinfunction "1_1") (pintype "passive"))
      (node (ref "C18") (pin "1") (pinfunction "1_1") (pintype "passive"))
      (node (ref "C19") (pin "1") (pinfunction "1_1") (pintype "passive"))
      (node (ref "C20") (pin "1") (pinfunction "1_1") (pintype "passive"))
      (node (ref "C24") (pin "1") (pinfunction "1_1") (pintype "passive"))
      (node (ref "C25") (pin "1") (pinfunction "1_1") (pintype "passive"))
      (node (ref "C26") (pin "1") (pinfunction "1_1") (pintype "passive"))
      (node (ref "C27") (pin "1") (pinfunction "1_1") (pintype "passive"))
      (node (ref "C5") (pin "2") (pinfunction "2_2") (pintype "passive"))
      (node (ref "D1") (pin "6") (pinfunction "VCC_6") (pintype "passive"))
      (node (ref "D3") (pin "6") (pinfunction "VCC_6") (pintype "passive"))
      (node (ref "J1") (pin "4") (pinfunction "IN_4") (pintype "passive"))
      (node (ref "R1") (pin "1") (pinfunction "1_1") (pintype "passive"))
      (node (ref "R4") (pin "1") (pinfunction "1_1") (pintype "passive"))
      (node (ref "X1") (pin "1") (pinfunction "1_1") (pintype "passive"))
    )
    (net (code "4") (name "+LED") (class "Default")
      (node (ref "C21") (pin "1") (pinfunction "1_1") (pintype "passive"))
      (node (ref "C22") (pin "1") (pinfunction "1_1") (pintype "passive"))
      (node (ref "C23") (pin "1") (pinfunction "1_1") (pintype "passive"))
      (node (ref "C8") (pin "2") (pinfunction "2_2") (pintype "passive"))
      (node (ref "L2") (pin "1") (pinfunction "1_1") (pintype "passive"))
      (node (ref "R8") (pin "1") (pinfunction "1_1") (pintype "passive"))
      (node (ref "R8") (pin "2") (pinfunction "2_2") (pintype "passive"))
      (node (ref "X6") (pin "2") (pinfunction "2_2") (pintype "passive"))
    )
    (net (code "5") (name "/BASE_KEY_RELAY_START") (class "Default")
      (node (ref "D4") (pin "2") (pinfunction "A0_ADC0_2") (pintype "input"))
      (node (ref "R13") (pin "2") (pinfunction "2_2") (pintype "passive"))
    )
    (net (code "6") (name "/BUT_LED") (class "Default")
      (node (ref "C13") (pin "2") (pinfunction "2_2") (pintype "passive"))
      (node (ref "D4") (pin "4") (pinfunction "D5_GPIO14_4") (pintype "bidirectional"))
      (node (ref "R12") (pin "1") (pinfunction "1_1") (pintype "passive"))
      (node (ref "X7") (pin "1") (pinfunction "1_1") (pintype "passive"))
    )
    (net (code "7") (name "/BUT_TRIG") (class "Default")
      (node (ref "C14") (pin "2") (pinfunction "2_2") (pintype "passive"))
      (node (ref "D4") (pin "6") (pinfunction "D7_GPIO13_6") (pintype "bidirectional"))
      (node (ref "R14") (pin "1") (pinfunction "1_1") (pintype "passive"))
      (node (ref "X9") (pin "1") (pinfunction "1_1") (pintype "passive"))
    )
    (net (code "8") (name "/LED_BUTS") (class "Default")
      (node (ref "D4") (pin "5") (pinfunction "D6_GPIO12_5") (pintype "bidirectional"))
      (node (ref "R15") (pin "2") (pinfunction "2_2") (pintype "passive"))
    )
    (net (code "9") (name "/LED_BUTT") (class "Default")
      (node (ref "D4") (pin "12") (pinfunction "D3_GPIO0_12") (pintype "bidirectional"))
      (node (ref "R17") (pin "2") (pinfunction "2_2") (pintype "passive"))
    )
    (net (code "11") (name "/LED_BUT_LED") (class "Default")
      (node (ref "D4") (pin "7") (pinfunction "D8_GPIO15_7") (pintype "bidirectional"))
      (node (ref "R16") (pin "2") (pinfunction "2_2") (pintype "passive"))
    )
    (net (code "12") (name "/LED_PWM") (class "Default")
      (node (ref "D4") (pin "14") (pinfunction "D1_GPIO5_14") (pintype "bidirectional"))
      (node (ref "R11") (pin "2") (pinfunction "2_2") (pintype "passive"))
    )
    (net (code "13") (name "/RELAY_POWER") (class "Default")
      (node (ref "K1") (pin "1") (pinfunction "1_1") (pintype "passive"))
      (node (ref "VD3") (pin "1") (pinfunction "1_1") (pintype "passive"))
      (node (ref "VT3") (pin "3") (pinfunction "C_3") (pintype "passive"))
    )
    (net (code "14") (name "/SIGNAL") (class "Default")
      (node (ref "D4") (pin "3") (pinfunction "D0_GPIO16_3") (pintype "bidirectional"))
      (node (ref "R7") (pin "1") (pinfunction "1_1") (pintype "passive"))
    )
    (net (code "15") (name "GND") (class "Default")
      (node (ref "C1") (pin "1") (pinfunction "1_1") (pintype "passive"))
      (node (ref "C10") (pin "1") (pinfunction "1_1") (pintype "passive"))
      (node (ref "C11") (pin "2") (pinfunction "2_2") (pintype "passive"))
      (node (ref "C12") (pin "1") (pinfunction "1_1") (pintype "passive"))
      (node (ref "C13") (pin "1") (pinfunction "1_1") (pintype "passive"))
      (node (ref "C14") (pin "1") (pinfunction "1_1") (pintype "passive"))
      (node (ref "C15") (pin "2") (pinfunction "2_2") (pintype "passive"))
      (node (ref "C16") (pin "2") (pinfunction "2_2") (pintype "passive"))
      (node (ref "C17") (pin "2") (pinfunction "2_2") (pintype "passive"))
      (node (ref "C18") (pin "2") (pinfunction "2_2") (pintype "passive"))
      (node (ref "C19") (pin "2") (pinfunction "2_2") (pintype "passive"))
      (node (ref "C2") (pin "1") (pinfunction "1_1") (pintype "passive"))
      (node (ref "C20") (pin "2") (pinfunction "2_2") (pintype "passive"))
      (node (ref "C21") (pin "2") (pinfunction "2_2") (pintype "passive"))
      (node (ref "C22") (pin "2") (pinfunction "2_2") (pintype "passive"))
      (node (ref "C23") (pin "2") (pinfunction "2_2") (pintype "passive"))
      (node (ref "C24") (pin "2") (pinfunction "2_2") (pintype "passive"))
      (node (ref "C25") (pin "2") (pinfunction "2_2") (pintype "passive"))
      (node (ref "C26") (pin "2") (pinfunction "2_2") (pintype "passive"))
      (node (ref "C27") (pin "2") (pinfunction "2_2") (pintype "passive"))
      (node (ref "C3") (pin "2") (pinfunction "2_2") (pintype "passive"))
      (node (ref "C4") (pin "2") (pinfunction "2_2") (pintype "passive"))
      (node (ref "C5") (pin "1") (pinfunction "1_1") (pintype "passive"))
      (node (ref "C6") (pin "2") (pinfunction "2_2") (pintype "passive"))
      (node (ref "C7") (pin "1") (pinfunction "1_1") (pintype "passive"))
      (node (ref "C8") (pin "1") (pinfunction "1_1") (pintype "passive"))
      (node (ref "C9") (pin "2") (pinfunction "2_2") (pintype "passive"))
      (node (ref "D1") (pin "4") (pinfunction "GND_4") (pintype "passive"))
      (node (ref "D2") (pin "1") (pinfunction "GND_1") (pintype "power_in"))
      (node (ref "D3") (pin "4") (pinfunction "GND_4") (pintype "passive"))
      (node (ref "D4") (pin "10") (pinfunction "GND_10") (pintype "power_in"))
      (node (ref "R10") (pin "1") (pinfunction "1_1") (pintype "passive"))
      (node (ref "R3") (pin "1") (pinfunction "1_1") (pintype "passive"))
      (node (ref "U1") (pin "3") (pinfunction "E_3") (pintype "passive"))
      (node (ref "VD1") (pin "1") (pinfunction "1_1") (pintype "passive"))
      (node (ref "VD2") (pin "1") (pinfunction "1_1") (pintype "passive"))
      (node (ref "VT1") (pin "3") (pinfunction "S_3") (pintype "passive"))
      (node (ref "VT2") (pin "2") (pinfunction "E_2") (pintype "passive"))
      (node (ref "VT3") (pin "2") (pinfunction "E_2") (pintype "passive"))
      (node (ref "VT4") (pin "2") (pinfunction "E_2") (pintype "passive"))
      (node (ref "VT5") (pin "2") (pinfunction "E_2") (pintype "passive"))
      (node (ref "VT6") (pin "2") (pinfunction "E_2") (pintype "passive"))
      (node (ref "X1") (pin "2") (pinfunction "2_2") (pintype "passive"))
      (node (ref "X7") (pin "2") (pinfunction "2_2") (pintype "passive"))
      (node (ref "X9") (pin "2") (pinfunction "2_2") (pintype "passive"))
    )
    (net (code "16") (name "Net-(D1-Comp_Inverting_input)") (class "Default")
      (node (ref "D1") (pin "5") (pinfunction "Comp_Inverting_input_5") (pintype "passive"))
      (node (ref "R2") (pin "3") (pinfunction "3_3") (pintype "passive"))
      (node (ref "R3") (pin "2") (pinfunction "2_2") (pintype "passive"))
    )
    (net (code "17") (name "Net-(D1-Driver_Collector)") (class "Default")
      (node (ref "D1") (pin "1") (pinfunction "Switch_Collector_1") (pintype "passive"))
      (node (ref "D1") (pin "7") (pinfunction "PEAK_Sense_7") (pintype "passive"))
      (node (ref "D1") (pin "8") (pinfunction "Driver_Collector_8") (pintype "passive"))
      (node (ref "R1") (pin "2") (pinfunction "2_2") (pintype "passive"))
    )
    (net (code "18") (name "Net-(D1-Switch_Emitter)") (class "Default")
      (node (ref "D1") (pin "2") (pinfunction "Switch_Emitter_2") (pintype "passive"))
      (node (ref "L1") (pin "2") (pinfunction "2_2") (pintype "passive"))
      (node (ref "VD1") (pin "2") (pinfunction "2_2") (pintype "passive"))
    )
    (net (code "19") (name "Net-(D1-Timing_Capacitor)") (class "Default")
      (node (ref "C7") (pin "2") (pinfunction "2_2") (pintype "passive"))
      (node (ref "D1") (pin "3") (pinfunction "Timing_Capacitor_3") (pintype "passive"))
    )
    (net (code "20") (name "Net-(D3-Comp_Inverting_input)") (class "Default")
      (node (ref "D3") (pin "5") (pinfunction "Comp_Inverting_input_5") (pintype "passive"))
      (node (ref "R10") (pin "2") (pinfunction "2_2") (pintype "passive"))
      (node (ref "R8") (pin "3") (pinfunction "3_3") (pintype "passive"))
    )
    (net (code "21") (name "Net-(D3-Driver_Collector)") (class "Default")
      (node (ref "D3") (pin "1") (pinfunction "Switch_Collector_1") (pintype "passive"))
      (node (ref "D3") (pin "7") (pinfunction "PEAK_Sense_7") (pintype "passive"))
      (node (ref "D3") (pin "8") (pinfunction "Driver_Collector_8") (pintype "passive"))
      (node (ref "R4") (pin "2") (pinfunction "2_2") (pintype "passive"))
    )
    (net (code "22") (name "Net-(D3-Switch_Emitter)") (class "Default")
      (node (ref "D3") (pin "2") (pinfunction "Switch_Emitter_2") (pintype "passive"))
      (node (ref "L2") (pin "2") (pinfunction "2_2") (pintype "passive"))
      (node (ref "VD2") (pin "2") (pinfunction "2_2") (pintype "passive"))
    )
    (net (code "23") (name "Net-(D3-Timing_Capacitor)") (class "Default")
      (node (ref "C12") (pin "2") (pinfunction "2_2") (pintype "passive"))
      (node (ref "D3") (pin "3") (pinfunction "Timing_Capacitor_3") (pintype "passive"))
    )
    (net (code "24") (name "Net-(D4-3.3V)") (class "Default")
      (node (ref "D4") (pin "8") (pinfunction "3.3V_8") (pintype "power_in"))
      (node (ref "J2") (pin "1") (pinfunction "IN_1") (pintype "passive"))
    )
    (net (code "25") (name "Net-(D4-5V)") (class "Default")
      (node (ref "D4") (pin "9") (pinfunction "5V_9") (pintype "power_in"))
      (node (ref "J3") (pin "1") (pinfunction "IN_1") (pintype "passive"))
    )
    (net (code "26") (name "Net-(J1-IN-Pad1)") (class "Default")
      (node (ref "J1") (pin "1") (pinfunction "IN_1") (pintype "passive"))
      (node (ref "J1") (pin "3") (pinfunction "IN_3") (pintype "passive"))
      (node (ref "R9") (pin "2") (pinfunction "2_2") (pintype "passive"))
    )
    (net (code "27") (name "Net-(K1-Pad3)") (class "Default")
      (node (ref "K1") (pin "3") (pinfunction "3_3") (pintype "passive"))
      (node (ref "X3") (pin "1") (pinfunction "1_1") (pintype "passive"))
      (node (ref "X4") (pin "2") (pinfunction "2_2") (pintype "passive"))
    )
    (net (code "28") (name "Net-(K1-Pad4)") (class "Default")
      (node (ref "K1") (pin "4") (pinfunction "4_4") (pintype "passive"))
      (node (ref "X2") (pin "2") (pinfunction "2_2") (pintype "passive"))
      (node (ref "X4") (pin "1") (pinfunction "1_1") (pintype "passive"))
    )
    (net (code "29") (name "Net-(R5-Pad1)") (class "Default")
      (node (ref "R5") (pin "1") (pinfunction "1_1") (pintype "passive"))
      (node (ref "R7") (pin "2") (pinfunction "2_2") (pintype "passive"))
      (node (ref "U1") (pin "4") (pinfunction "C_4") (pintype "passive"))
    )
    (net (code "30") (name "Net-(R6-Pad1)") (class "Default")
      (node (ref "R6") (pin "1") (pinfunction "1_1") (pintype "passive"))
      (node (ref "X5") (pin "2") (pinfunction "2_2") (pintype "passive"))
    )
    (net (code "31") (name "Net-(U1-A)") (class "Default")
      (node (ref "R6") (pin "2") (pinfunction "2_2") (pintype "passive"))
      (node (ref "U1") (pin "1") (pinfunction "A_1") (pintype "passive"))
    )
    (net (code "32") (name "Net-(U1-C-Pad2)") (class "Default")
      (node (ref "U1") (pin "2") (pinfunction "C_2") (pintype "passive"))
      (node (ref "X5") (pin "1") (pinfunction "1_1") (pintype "passive"))
    )
    (net (code "33") (name "Net-(VT1-D)") (class "Default")
      (node (ref "VT1") (pin "2") (pinfunction "D_2") (pintype "passive"))
      (node (ref "X6") (pin "1") (pinfunction "1_1") (pintype "passive"))
    )
    (net (code "34") (name "Net-(VT1-G)") (class "Default")
      (node (ref "R9") (pin "1") (pinfunction "1_1") (pintype "passive"))
      (node (ref "VT1") (pin "1") (pinfunction "G_1") (pintype "passive"))
      (node (ref "VT2") (pin "3") (pinfunction "C_3") (pintype "passive"))
    )
    (net (code "35") (name "Net-(VT2-B)") (class "Default")
      (node (ref "R11") (pin "1") (pinfunction "1_1") (pintype "passive"))
      (node (ref "VT2") (pin "1") (pinfunction "B_1") (pintype "passive"))
    )
    (net (code "36") (name "Net-(VT3-B)") (class "Default")
      (node (ref "R13") (pin "1") (pinfunction "1_1") (pintype "passive"))
      (node (ref "VT3") (pin "1") (pinfunction "B_1") (pintype "passive"))
    )
    (net (code "37") (name "Net-(VT4-B)") (class "Default")
      (node (ref "R15") (pin "1") (pinfunction "1_1") (pintype "passive"))
      (node (ref "VT4") (pin "1") (pinfunction "B_1") (pintype "passive"))
    )
    (net (code "38") (name "Net-(VT4-C)") (class "Default")
      (node (ref "VT4") (pin "3") (pinfunction "C_3") (pintype "passive"))
      (node (ref "X8") (pin "2") (pinfunction "2_2") (pintype "passive"))
    )
    (net (code "39") (name "Net-(VT5-B)") (class "Default")
      (node (ref "R16") (pin "1") (pinfunction "1_1") (pintype "passive"))
      (node (ref "VT5") (pin "1") (pinfunction "B_1") (pintype "passive"))
    )
    (net (code "40") (name "Net-(VT5-C)") (class "Default")
      (node (ref "VT5") (pin "3") (pinfunction "C_3") (pintype "passive"))
      (node (ref "X10") (pin "2") (pinfunction "2_2") (pintype "passive"))
    )
    (net (code "41") (name "Net-(VT6-B)") (class "Default")
      (node (ref "R17") (pin "1") (pinfunction "1_1") (pintype "passive"))
      (node (ref "VT6") (pin "1") (pinfunction "B_1") (pintype "passive"))
    )
    (net (code "42") (name "Net-(VT6-C)") (class "Default")
      (node (ref "VT6") (pin "3") (pinfunction "C_3") (pintype "passive"))
      (node (ref "X11") (pin "2") (pinfunction "2_2") (pintype "passive"))
    )
    (net (code "43") (name "Net-(X2-Pad1)") (class "Default")
      (node (ref "X2") (pin "1") (pinfunction "1_1") (pintype "passive"))
      (node (ref "X3") (pin "2") (pinfunction "2_2") (pintype "passive"))
    )
    (net (code "44") (name "unconnected-(D4-D2_GPIO4-Pad13)") (class "Default")
      (node (ref "D4") (pin "13") (pinfunction "D2_GPIO4_13") (pintype "bidirectional"))
    )
    (net (code "45") (name "unconnected-(D4-D4_GPIO2-Pad11)") (class "Default")
      (node (ref "D4") (pin "11") (pinfunction "D4_GPIO2_11") (pintype "bidirectional"))
    )
    (net (code "46") (name "unconnected-(D4-RESET-Pad1)") (class "Default")
      (node (ref "D4") (pin "1") (pinfunction "RESET_1") (pintype "input"))
    )
    (net (code "47") (name "unconnected-(D4-RX_GPIO3-Pad15)") (class "Default")
      (node (ref "D4") (pin "15") (pinfunction "RX_GPIO3_15") (pintype "bidirectional"))
    )
    (net (code "48") (name "unconnected-(D4-TX_GPIO1-Pad16)") (class "Default")
      (node (ref "D4") (pin "16") (pinfunction "TX_GPIO1_16") (pintype "bidirectional"))
    )
    (net (code "49") (name "unconnected-(K1-Pad5)") (class "Default")
      (node (ref "K1") (pin "5") (pinfunction "5_5") (pintype "passive"))
    )
  )
)
